# Schematic.net
KiCad netlist of a schematic drawn in EAGLE
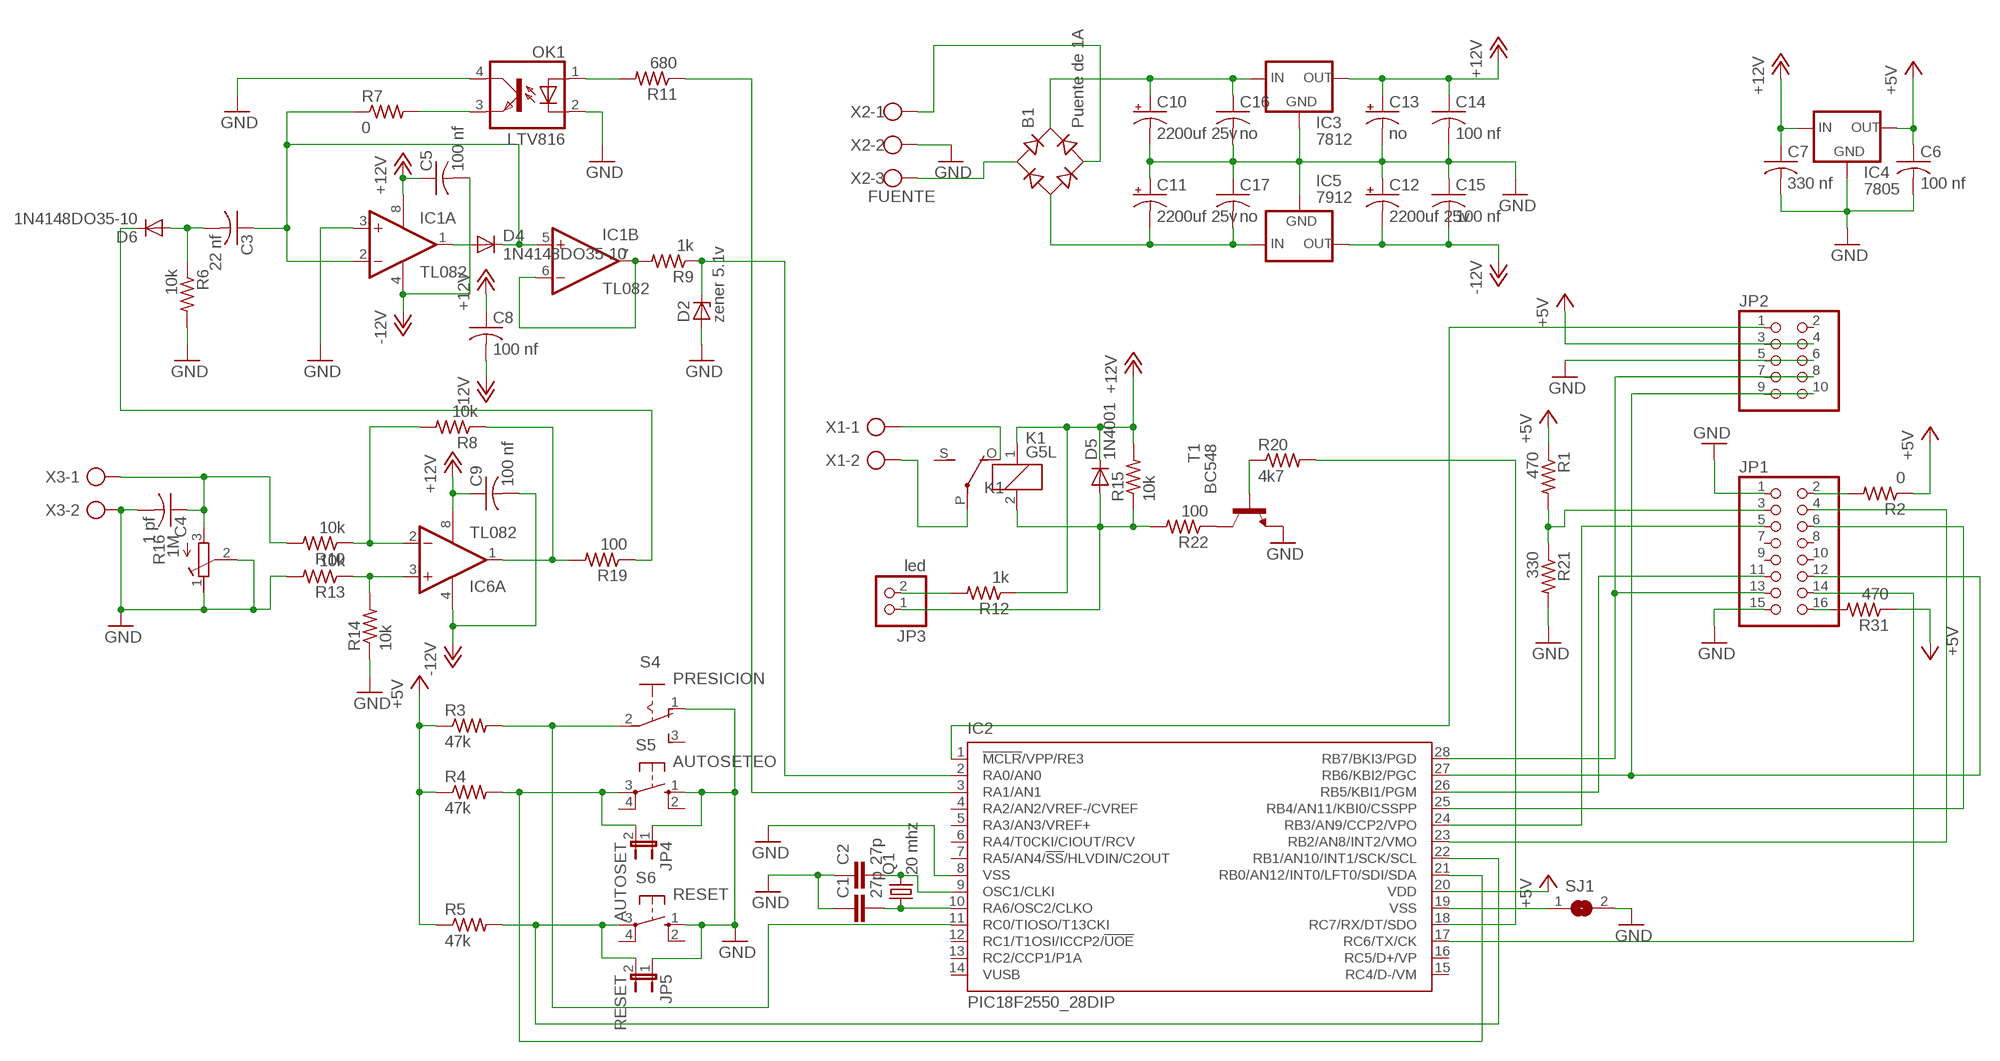
[diagram p0: schematic, sheet 1]

(export (version "E")
  (design (tool "Eeschema 10.0.6"))
  (components
    (comp (ref "B1")
      (value "Puente de 1A")
      (footprint "eagle-import:RB1A")
      (libsource (lib "eagle-import") (part "RB1A"))
    )
    (comp (ref "C1")
      (value "27p")
      (footprint "eagle-import:C050-024X044")
      (libsource (lib "eagle-import") (part "C-EU050-024X044"))
    )
    (comp (ref "C2")
      (value "27p")
      (footprint "eagle-import:C050-024X044")
      (libsource (lib "eagle-import") (part "C-EU050-024X044"))
    )
    (comp (ref "C3")
      (value "22 nf")
      (footprint "eagle-import:C050-024X044")
      (libsource (lib "eagle-import") (part "C-US050-024X044"))
    )
    (comp (ref "C4")
      (value "1 pf")
      (footprint "eagle-import:C050-024X044")
      (libsource (lib "eagle-import") (part "C-US050-024X044"))
    )
    (comp (ref "C5")
      (value "100 nf")
      (footprint "eagle-import:C050-024X044")
      (libsource (lib "eagle-import") (part "C-US050-024X044"))
    )
    (comp (ref "C6")
      (value "100 nf")
      (footprint "eagle-import:C050-024X044")
      (libsource (lib "eagle-import") (part "C-US050-024X044"))
    )
    (comp (ref "C7")
      (value "330 nf")
      (footprint "eagle-import:C050-024X044")
      (libsource (lib "eagle-import") (part "C-US050-024X044"))
    )
    (comp (ref "C8")
      (value "100 nf")
      (footprint "eagle-import:C050-024X044")
      (libsource (lib "eagle-import") (part "C-US050-024X044"))
    )
    (comp (ref "C9")
      (value "100 nf")
      (footprint "eagle-import:C050-024X044")
      (libsource (lib "eagle-import") (part "C-US050-024X044"))
    )
    (comp (ref "C10")
      (value "2200uf 25v")
      (footprint "eagle-import:E7,5-16")
      (libsource (lib "eagle-import") (part "CPOL-USE7.5-16"))
    )
    (comp (ref "C11")
      (value "2200uf 25v")
      (footprint "eagle-import:E7,5-16")
      (libsource (lib "eagle-import") (part "CPOL-USE7.5-16"))
    )
    (comp (ref "C12")
      (value "2200uf 25v")
      (footprint "eagle-import:E7,5-16")
      (libsource (lib "eagle-import") (part "CPOL-USE7.5-16"))
    )
    (comp (ref "C13")
      (value "no")
      (footprint "eagle-import:E7,5-16")
      (libsource (lib "eagle-import") (part "CPOL-USE7.5-16"))
    )
    (comp (ref "C14")
      (value "100 nf")
      (footprint "eagle-import:C050-024X044")
      (libsource (lib "eagle-import") (part "C-US050-024X044"))
    )
    (comp (ref "C15")
      (value "100 nf")
      (footprint "eagle-import:C050-024X044")
      (libsource (lib "eagle-import") (part "C-US050-024X044"))
    )
    (comp (ref "C16")
      (value "no")
      (footprint "eagle-import:C050-024X044")
      (libsource (lib "eagle-import") (part "C-US050-024X044"))
    )
    (comp (ref "C17")
      (value "no")
      (footprint "eagle-import:C050-024X044")
      (libsource (lib "eagle-import") (part "C-US050-024X044"))
    )
    (comp (ref "D2")
      (value "zener 5.1v")
      (footprint "eagle-import:P1Z12")
      (libsource (lib "eagle-import") (part "ZENER-DIODEP1-Z12"))
    )
    (comp (ref "D4")
      (value "1N4148DO35-10")
      (footprint "eagle-import:DO35-10")
      (libsource (lib "eagle-import") (part "1N4148DO35-10"))
    )
    (comp (ref "D5")
      (value "1N4001")
      (footprint "eagle-import:DO41-10")
      (libsource (lib "eagle-import") (part "1N4004"))
    )
    (comp (ref "D6")
      (value "1N4148DO35-10")
      (footprint "eagle-import:DO35-10")
      (libsource (lib "eagle-import") (part "1N4148DO35-10"))
    )
    (comp (ref "IC1")
      (value "TL082")
      (footprint "eagle-import:DIL08")
      (libsource (lib "eagle-import") (part "4558NLM"))
    )
    (comp (ref "IC2")
      (value "PIC18F2550_28DIP")
      (footprint "eagle-import:DIL28-3")
      (libsource (lib "eagle-import") (part "PIC18F2_28DIP550"))
    )
    (comp (ref "IC3")
      (value "7812")
      (footprint "eagle-import:78XXS")
      (libsource (lib "eagle-import") (part "78XXS"))
    )
    (comp (ref "IC4")
      (value "7805")
      (footprint "eagle-import:78XXS")
      (libsource (lib "eagle-import") (part "78XXS"))
    )
    (comp (ref "IC5")
      (value "7912")
      (footprint "eagle-import:79XXS")
      (libsource (lib "eagle-import") (part "79XXS"))
    )
    (comp (ref "IC6")
      (value "TL082")
      (footprint "eagle-import:DIL08")
      (libsource (lib "eagle-import") (part "4558NLM"))
    )
    (comp (ref "JP1")
      (value "PINHD-2X8")
      (footprint "eagle-import:2X08")
      (libsource (lib "eagle-import") (part "PINHD-2X8"))
    )
    (comp (ref "JP2")
      (value "PINHD-2X5")
      (footprint "eagle-import:2X05")
      (libsource (lib "eagle-import") (part "PINHD-2X5"))
    )
    (comp (ref "JP3")
      (value "led")
      (footprint "eagle-import:1X02")
      (libsource (lib "eagle-import") (part "PINHD-1X2"))
    )
    (comp (ref "JP4")
      (value "AUTOSET")
      (footprint "eagle-import:JP1")
      (libsource (lib "eagle-import") (part "JP1E"))
    )
    (comp (ref "JP5")
      (value "RESET")
      (footprint "eagle-import:JP1")
      (libsource (lib "eagle-import") (part "JP1E"))
    )
    (comp (ref "K1")
      (value "G5L")
      (footprint "eagle-import:G5LE")
      (libsource (lib "eagle-import") (part "G5L"))
    )
    (comp (ref "OK1")
      (value "LTV816")
      (footprint "eagle-import:DIL04")
      (libsource (lib "eagle-import") (part "LTV816"))
    )
    (comp (ref "Q1")
      (value "20 mhz")
      (footprint "eagle-import:HC49_S")
      (libsource (lib "eagle-import") (part "CRYSTALHC49S"))
    )
    (comp (ref "R1")
      (value "470")
      (footprint "eagle-import:0207_10")
      (libsource (lib "eagle-import") (part "R-US_0207/10"))
    )
    (comp (ref "R2")
      (value "0")
      (footprint "eagle-import:0207_10")
      (libsource (lib "eagle-import") (part "R-US_0207/10"))
    )
    (comp (ref "R3")
      (value "47k")
      (footprint "eagle-import:0207_10")
      (libsource (lib "eagle-import") (part "R-US_0207/10"))
    )
    (comp (ref "R4")
      (value "47k")
      (footprint "eagle-import:0207_10")
      (libsource (lib "eagle-import") (part "R-US_0207/10"))
    )
    (comp (ref "R5")
      (value "47k")
      (footprint "eagle-import:0207_10")
      (libsource (lib "eagle-import") (part "R-US_0207/10"))
    )
    (comp (ref "R6")
      (value "10k")
      (footprint "eagle-import:0207_10")
      (libsource (lib "eagle-import") (part "R-US_0207/10"))
    )
    (comp (ref "R7")
      (value "0")
      (footprint "eagle-import:0207_10")
      (libsource (lib "eagle-import") (part "R-US_0207/10"))
    )
    (comp (ref "R8")
      (value "10k")
      (footprint "eagle-import:0207_10")
      (libsource (lib "eagle-import") (part "R-US_0207/10"))
    )
    (comp (ref "R9")
      (value "1k")
      (footprint "eagle-import:0207_10")
      (libsource (lib "eagle-import") (part "R-US_0207/10"))
    )
    (comp (ref "R10")
      (value "10k")
      (footprint "eagle-import:0207_10")
      (libsource (lib "eagle-import") (part "R-US_0207/10"))
    )
    (comp (ref "R11")
      (value "680")
      (footprint "eagle-import:0207_10")
      (libsource (lib "eagle-import") (part "R-US_0207/10"))
    )
    (comp (ref "R12")
      (value "1k")
      (footprint "eagle-import:0207_10")
      (libsource (lib "eagle-import") (part "R-US_0207/10"))
    )
    (comp (ref "R13")
      (value "10k")
      (footprint "eagle-import:0207_10")
      (libsource (lib "eagle-import") (part "R-US_0207/10"))
    )
    (comp (ref "R14")
      (value "10k")
      (footprint "eagle-import:0207_10")
      (libsource (lib "eagle-import") (part "R-US_0207/10"))
    )
    (comp (ref "R15")
      (value "10k")
      (footprint "eagle-import:0207_10")
      (libsource (lib "eagle-import") (part "R-US_0207/10"))
    )
    (comp (ref "R16")
      (value "1M")
      (footprint "eagle-import:RTRIMT93YA")
      (libsource (lib "eagle-import") (part "R-TRIMMT93YA"))
    )
    (comp (ref "R19")
      (value "100")
      (footprint "eagle-import:0207_10")
      (libsource (lib "eagle-import") (part "R-US_0207/10"))
    )
    (comp (ref "R20")
      (value "4k7")
      (footprint "eagle-import:0207_10")
      (libsource (lib "eagle-import") (part "R-US_0207/10"))
    )
    (comp (ref "R21")
      (value "330")
      (footprint "eagle-import:0207_10")
      (libsource (lib "eagle-import") (part "R-US_0207/10"))
    )
    (comp (ref "R22")
      (value "100")
      (footprint "eagle-import:0207_10")
      (libsource (lib "eagle-import") (part "R-US_0207/10"))
    )
    (comp (ref "R31")
      (value "470")
      (footprint "eagle-import:0207_10")
      (libsource (lib "eagle-import") (part "R-US_0207/10"))
    )
    (comp (ref "S4")
      (value "PRESICION")
      (footprint "eagle-import:M251")
      (libsource (lib "eagle-import") (part "M251"))
    )
    (comp (ref "S5")
      (value "AUTOSETEO")
      (footprint "eagle-import:B3F-10XX")
      (libsource (lib "eagle-import") (part "10-XX"))
    )
    (comp (ref "S6")
      (value "RESET")
      (footprint "eagle-import:B3F-10XX")
      (libsource (lib "eagle-import") (part "10-XX"))
    )
    (comp (ref "SJ1") (value "SJ") (footprint "eagle-import:SJ") (libsource (lib "eagle-import") (part "SJ")))
    (comp (ref "T1")
      (value "BC548")
      (footprint "eagle-import:TO92")
      (libsource (lib "eagle-import") (part "BC547"))
    )
    (comp (ref "X1")
      (value "AK300/2")
      (footprint "eagle-import:AK300_2")
      (libsource (lib "eagle-import") (part "AK300/2"))
    )
    (comp (ref "X2")
      (value "FUENTE")
      (footprint "eagle-import:W237-103")
      (libsource (lib "eagle-import") (part "W237-103"))
    )
    (comp (ref "X3")
      (value "AK300/2")
      (footprint "eagle-import:AK300_2")
      (libsource (lib "eagle-import") (part "AK300/2"))
    )
  )
  (nets
    (net (code "1") (name "+5V") (class "Default")
      (node (ref "C6") (pin "1") (pinfunction "1_1") (pintype "passive"))
      (node (ref "IC2") (pin "20") (pinfunction "VDD_20") (pintype "power_in"))
      (node (ref "IC4") (pin "OUT") (pinfunction "OUT_OUT") (pintype "passive"))
      (node (ref "JP2") (pin "3") (pinfunction "3_3") (pintype "passive"))
      (node (ref "JP2") (pin "4") (pinfunction "4_4") (pintype "passive"))
      (node (ref "R1") (pin "1") (pinfunction "1_1") (pintype "passive"))
      (node (ref "R2") (pin "1") (pinfunction "1_1") (pintype "passive"))
      (node (ref "R3") (pin "1") (pinfunction "1_1") (pintype "passive"))
      (node (ref "R31") (pin "1") (pinfunction "1_1") (pintype "passive"))
      (node (ref "R4") (pin "1") (pinfunction "1_1") (pintype "passive"))
      (node (ref "R5") (pin "1") (pinfunction "1_1") (pintype "passive"))
    )
    (net (code "2") (name "+12V") (class "Default")
      (node (ref "C13") (pin "+") (pinfunction "+_+") (pintype "passive"))
      (node (ref "C14") (pin "1") (pinfunction "1_1") (pintype "passive"))
      (node (ref "C5") (pin "1") (pinfunction "1_1") (pintype "passive"))
      (node (ref "C7") (pin "1") (pinfunction "1_1") (pintype "passive"))
      (node (ref "C8") (pin "1") (pinfunction "1_1") (pintype "passive"))
      (node (ref "C9") (pin "1") (pinfunction "1_1") (pintype "passive"))
      (node (ref "D5") (pin "C") (pinfunction "C_C") (pintype "passive"))
      (node (ref "IC1") (pin "8") (pinfunction "V+_8") (pintype "power_in"))
      (node (ref "IC3") (pin "OUT") (pinfunction "OUT_OUT") (pintype "passive"))
      (node (ref "IC4") (pin "IN") (pinfunction "IN_IN") (pintype "input"))
      (node (ref "IC6") (pin "8") (pinfunction "V+_8") (pintype "power_in"))
      (node (ref "K1") (pin "1") (pinfunction "1_1") (pintype "passive"))
      (node (ref "R12") (pin "1") (pinfunction "1_1") (pintype "passive"))
      (node (ref "R15") (pin "2") (pinfunction "2_2") (pintype "passive"))
    )
    (net (code "3") (name "-12V") (class "Default")
      (node (ref "C12") (pin "-") (pinfunction "-_-") (pintype "passive"))
      (node (ref "C15") (pin "2") (pinfunction "2_2") (pintype "passive"))
      (node (ref "C5") (pin "2") (pinfunction "2_2") (pintype "passive"))
      (node (ref "C8") (pin "2") (pinfunction "2_2") (pintype "passive"))
      (node (ref "C9") (pin "2") (pinfunction "2_2") (pintype "passive"))
      (node (ref "IC1") (pin "4") (pinfunction "V-_4") (pintype "power_in"))
      (node (ref "IC5") (pin "OUT") (pinfunction "OUT_OUT") (pintype "passive"))
      (node (ref "IC6") (pin "4") (pinfunction "V-_4") (pintype "power_in"))
    )
    (net (code "4") (name "GND") (class "Default")
      (node (ref "C1") (pin "1") (pinfunction "1_1") (pintype "passive"))
      (node (ref "C10") (pin "-") (pinfunction "-_-") (pintype "passive"))
      (node (ref "C11") (pin "+") (pinfunction "+_+") (pintype "passive"))
      (node (ref "C12") (pin "+") (pinfunction "+_+") (pintype "passive"))
      (node (ref "C13") (pin "-") (pinfunction "-_-") (pintype "passive"))
      (node (ref "C14") (pin "2") (pinfunction "2_2") (pintype "passive"))
      (node (ref "C15") (pin "1") (pinfunction "1_1") (pintype "passive"))
      (node (ref "C16") (pin "2") (pinfunction "2_2") (pintype "passive"))
      (node (ref "C17") (pin "1") (pinfunction "1_1") (pintype "passive"))
      (node (ref "C2") (pin "1") (pinfunction "1_1") (pintype "passive"))
      (node (ref "C4") (pin "2") (pinfunction "2_2") (pintype "passive"))
      (node (ref "C6") (pin "2") (pinfunction "2_2") (pintype "passive"))
      (node (ref "C7") (pin "2") (pinfunction "2_2") (pintype "passive"))
      (node (ref "D2") (pin "A") (pinfunction "A_A") (pintype "passive"))
      (node (ref "IC1") (pin "3") (pinfunction "+IN_3") (pintype "input"))
      (node (ref "IC2") (pin "8") (pinfunction "VSS_8") (pintype "power_in"))
      (node (ref "IC3") (pin "GND") (pinfunction "GND_GND") (pintype "input"))
      (node (ref "IC4") (pin "GND") (pinfunction "GND_GND") (pintype "input"))
      (node (ref "IC5") (pin "GND") (pinfunction "GND_GND") (pintype "input"))
      (node (ref "JP1") (pin "1") (pinfunction "1_1") (pintype "passive"))
      (node (ref "JP1") (pin "15") (pinfunction "15_15") (pintype "passive"))
      (node (ref "JP2") (pin "5") (pinfunction "5_5") (pintype "passive"))
      (node (ref "JP2") (pin "6") (pinfunction "6_6") (pintype "passive"))
      (node (ref "JP4") (pin "1") (pinfunction "1_1") (pintype "passive"))
      (node (ref "JP5") (pin "1") (pinfunction "1_1") (pintype "passive"))
      (node (ref "OK1") (pin "2") (pinfunction "C_2") (pintype "passive"))
      (node (ref "OK1") (pin "4") (pinfunction "COL_4") (pintype "passive"))
      (node (ref "R13") (pin "2") (pinfunction "2_2") (pintype "passive"))
      (node (ref "R14") (pin "1") (pinfunction "1_1") (pintype "passive"))
      (node (ref "R16") (pin "1") (pinfunction "A_1") (pintype "passive"))
      (node (ref "R16") (pin "2") (pinfunction "S_2") (pintype "passive"))
      (node (ref "R21") (pin "2") (pinfunction "2_2") (pintype "passive"))
      (node (ref "R6") (pin "2") (pinfunction "2_2") (pintype "passive"))
      (node (ref "S4") (pin "1") (pinfunction "O_1") (pintype "passive"))
      (node (ref "S5") (pin "1") (pinfunction "S_1") (pintype "passive"))
      (node (ref "S6") (pin "1") (pinfunction "S_1") (pintype "passive"))
      (node (ref "SJ1") (pin "2") (pinfunction "2_2") (pintype "passive"))
      (node (ref "T1") (pin "1") (pinfunction "E_1") (pintype "passive"))
      (node (ref "X2") (pin "2") (pinfunction "KL_2") (pintype "passive"))
      (node (ref "X3") (pin "2") (pinfunction "KL_2") (pintype "passive"))
    )
    (net (code "5") (name "Net-(B1-Pad+)") (class "Default")
      (node (ref "B1") (pin "+") (pinfunction "+_+") (pintype "passive"))
      (node (ref "C10") (pin "+") (pinfunction "+_+") (pintype "passive"))
      (node (ref "C16") (pin "1") (pinfunction "1_1") (pintype "passive"))
      (node (ref "IC3") (pin "IN") (pinfunction "IN_IN") (pintype "input"))
    )
    (net (code "6") (name "Net-(B1-Pad-)") (class "Default")
      (node (ref "B1") (pin "-") (pinfunction "-_-") (pintype "passive"))
      (node (ref "C11") (pin "-") (pinfunction "-_-") (pintype "passive"))
      (node (ref "C17") (pin "2") (pinfunction "2_2") (pintype "passive"))
      (node (ref "IC5") (pin "IN") (pinfunction "IN_IN") (pintype "input"))
    )
    (net (code "7") (name "Net-(C3-Pad2)") (class "Default")
      (node (ref "C3") (pin "2") (pinfunction "2_2") (pintype "passive"))
      (node (ref "D6") (pin "A") (pinfunction "A_A") (pintype "passive"))
      (node (ref "R6") (pin "1") (pinfunction "1_1") (pintype "passive"))
    )
    (net (code "8") (name "Net-(D5-PadA)") (class "Default")
      (node (ref "D5") (pin "A") (pinfunction "A_A") (pintype "passive"))
      (node (ref "JP3") (pin "1") (pinfunction "1_1") (pintype "passive"))
      (node (ref "K1") (pin "2") (pinfunction "2_2") (pintype "passive"))
      (node (ref "R15") (pin "1") (pinfunction "1_1") (pintype "passive"))
      (node (ref "R22") (pin "2") (pinfunction "2_2") (pintype "passive"))
    )
    (net (code "9") (name "Net-(D6-PadC)") (class "Default")
      (node (ref "D6") (pin "C") (pinfunction "C_C") (pintype "passive"))
      (node (ref "R19") (pin "1") (pinfunction "1_1") (pintype "passive"))
    )
    (net (code "10") (name "Net-(IC1A--IN)") (class "Default")
      (node (ref "C3") (pin "1") (pinfunction "1_1") (pintype "passive"))
      (node (ref "D4") (pin "C") (pinfunction "C_C") (pintype "passive"))
      (node (ref "IC1") (pin "2") (pinfunction "-IN_2") (pintype "input"))
      (node (ref "IC1") (pin "5") (pinfunction "+IN_5") (pintype "input"))
      (node (ref "R7") (pin "1") (pinfunction "1_1") (pintype "passive"))
    )
    (net (code "11") (name "Net-(IC1A-OUT)") (class "Default")
      (node (ref "D4") (pin "A") (pinfunction "A_A") (pintype "passive"))
      (node (ref "IC1") (pin "1") (pinfunction "OUT_1") (pintype "output"))
    )
    (net (code "12") (name "Net-(IC1B--IN)") (class "Default")
      (node (ref "IC1") (pin "6") (pinfunction "-IN_6") (pintype "input"))
      (node (ref "IC1") (pin "7") (pinfunction "OUT_7") (pintype "output"))
      (node (ref "R9") (pin "2") (pinfunction "2_2") (pintype "passive"))
    )
    (net (code "13") (name "Net-(IC2-OSC1{slash}CLKI)") (class "Default")
      (node (ref "C2") (pin "2") (pinfunction "2_2") (pintype "passive"))
      (node (ref "IC2") (pin "9") (pinfunction "OSC1/CLKI_9") (pintype "input"))
      (node (ref "Q1") (pin "2") (pinfunction "2_2") (pintype "passive"))
    )
    (net (code "14") (name "Net-(IC2-RA0{slash}AN0)") (class "Default")
      (node (ref "D2") (pin "C") (pinfunction "C_C") (pintype "passive"))
      (node (ref "IC2") (pin "2") (pinfunction "RA0/AN0_2") (pintype "bidirectional"))
      (node (ref "R9") (pin "1") (pinfunction "1_1") (pintype "passive"))
    )
    (net (code "15") (name "Net-(IC2-RA1{slash}AN1)") (class "Default")
      (node (ref "IC2") (pin "3") (pinfunction "RA1/AN1_3") (pintype "bidirectional"))
      (node (ref "R11") (pin "1") (pinfunction "1_1") (pintype "passive"))
    )
    (net (code "16") (name "Net-(IC2-RA6{slash}OSC2{slash}CLKO)") (class "Default")
      (node (ref "C1") (pin "2") (pinfunction "2_2") (pintype "passive"))
      (node (ref "IC2") (pin "10") (pinfunction "RA6/OSC2/CLKO_10") (pintype "output"))
      (node (ref "Q1") (pin "1") (pinfunction "1_1") (pintype "passive"))
    )
    (net (code "17") (name "Net-(IC2-RB0{slash}AN12{slash}INT0{slash}LFT0{slash}SDI{slash}SDA)") (class "Default")
      (node (ref "IC2") (pin "21") (pinfunction "RB0/AN12/INT0/LFT0/SDI/SDA_21") (pintype "bidirectional"))
      (node (ref "JP4") (pin "2") (pinfunction "2_2") (pintype "passive"))
      (node (ref "R4") (pin "2") (pinfunction "2_2") (pintype "passive"))
      (node (ref "S5") (pin "3") (pinfunction "P_3") (pintype "passive"))
    )
    (net (code "18") (name "Net-(IC2-RB1{slash}AN10{slash}INT1{slash}SCK{slash}SCL)") (class "Default")
      (node (ref "IC2") (pin "22") (pinfunction "RB1/AN10/INT1/SCK/SCL_22") (pintype "bidirectional"))
      (node (ref "JP5") (pin "2") (pinfunction "2_2") (pintype "passive"))
      (node (ref "R5") (pin "2") (pinfunction "2_2") (pintype "passive"))
      (node (ref "S6") (pin "3") (pinfunction "P_3") (pintype "passive"))
    )
    (net (code "19") (name "Net-(IC2-RB2{slash}AN8{slash}INT2{slash}VMO)") (class "Default")
      (node (ref "IC2") (pin "23") (pinfunction "RB2/AN8/INT2/VMO_23") (pintype "bidirectional"))
      (node (ref "JP1") (pin "4") (pinfunction "4_4") (pintype "passive"))
    )
    (net (code "20") (name "Net-(IC2-RB3{slash}AN9{slash}CCP2{slash}VPO)") (class "Default")
      (node (ref "IC2") (pin "24") (pinfunction "RB3/AN9/CCP2/VPO_24") (pintype "bidirectional"))
      (node (ref "JP1") (pin "5") (pinfunction "5_5") (pintype "passive"))
    )
    (net (code "21") (name "Net-(IC2-RB4{slash}AN11{slash}KBI0{slash}CSSPP)") (class "Default")
      (node (ref "IC2") (pin "25") (pinfunction "RB4/AN11/KBI0/CSSPP_25") (pintype "bidirectional"))
      (node (ref "JP1") (pin "6") (pinfunction "6_6") (pintype "passive"))
    )
    (net (code "22") (name "Net-(IC2-RB5{slash}KBI1{slash}PGM)") (class "Default")
      (node (ref "IC2") (pin "26") (pinfunction "RB5/KBI1/PGM_26") (pintype "bidirectional"))
      (node (ref "JP1") (pin "11") (pinfunction "11_11") (pintype "passive"))
    )
    (net (code "23") (name "Net-(IC2-RB6{slash}KBI2{slash}PGC)") (class "Default")
      (node (ref "IC2") (pin "27") (pinfunction "RB6/KBI2/PGC_27") (pintype "bidirectional"))
      (node (ref "JP1") (pin "12") (pinfunction "12_12") (pintype "passive"))
      (node (ref "JP2") (pin "10") (pinfunction "10_10") (pintype "passive"))
      (node (ref "JP2") (pin "9") (pinfunction "9_9") (pintype "passive"))
    )
    (net (code "24") (name "Net-(IC2-RB7{slash}BKI3{slash}PGD)") (class "Default")
      (node (ref "IC2") (pin "28") (pinfunction "RB7/BKI3/PGD_28") (pintype "bidirectional"))
      (node (ref "JP1") (pin "13") (pinfunction "13_13") (pintype "passive"))
      (node (ref "JP2") (pin "7") (pinfunction "7_7") (pintype "passive"))
      (node (ref "JP2") (pin "8") (pinfunction "8_8") (pintype "passive"))
    )
    (net (code "25") (name "Net-(IC2-RC0{slash}TIOSO{slash}T13CKI)") (class "Default")
      (node (ref "IC2") (pin "11") (pinfunction "RC0/TIOSO/T13CKI_11") (pintype "bidirectional"))
      (node (ref "R3") (pin "2") (pinfunction "2_2") (pintype "passive"))
      (node (ref "S4") (pin "2") (pinfunction "P_2") (pintype "passive"))
    )
    (net (code "26") (name "Net-(IC2-RC6{slash}TX{slash}CK)") (class "Default")
      (node (ref "IC2") (pin "17") (pinfunction "RC6/TX/CK_17") (pintype "bidirectional"))
      (node (ref "JP1") (pin "14") (pinfunction "14_14") (pintype "passive"))
    )
    (net (code "27") (name "Net-(IC2-RC7{slash}RX{slash}DT{slash}SDO)") (class "Default")
      (node (ref "IC2") (pin "18") (pinfunction "RC7/RX/DT/SDO_18") (pintype "bidirectional"))
      (node (ref "R20") (pin "2") (pinfunction "2_2") (pintype "passive"))
    )
    (net (code "28") (name "Net-(IC2-VSS-Pad19)") (class "Default")
      (node (ref "IC2") (pin "19") (pinfunction "VSS_19") (pintype "power_in"))
      (node (ref "SJ1") (pin "1") (pinfunction "1_1") (pintype "passive"))
    )
    (net (code "29") (name "Net-(IC2-~{MCLR}{slash}VPP{slash}RE3)") (class "Default")
      (node (ref "IC2") (pin "1") (pinfunction "~{MCLR}/VPP/RE3_1") (pintype "input"))
      (node (ref "JP2") (pin "1") (pinfunction "1_1") (pintype "passive"))
    )
    (net (code "30") (name "Net-(IC6A-+IN)") (class "Default")
      (node (ref "IC6") (pin "3") (pinfunction "+IN_3") (pintype "input"))
      (node (ref "R13") (pin "1") (pinfunction "1_1") (pintype "passive"))
      (node (ref "R14") (pin "2") (pinfunction "2_2") (pintype "passive"))
    )
    (net (code "31") (name "Net-(IC6A--IN)") (class "Default")
      (node (ref "IC6") (pin "2") (pinfunction "-IN_2") (pintype "input"))
      (node (ref "R10") (pin "1") (pinfunction "1_1") (pintype "passive"))
      (node (ref "R8") (pin "2") (pinfunction "2_2") (pintype "passive"))
    )
    (net (code "32") (name "Net-(IC6A-OUT)") (class "Default")
      (node (ref "IC6") (pin "1") (pinfunction "OUT_1") (pintype "output"))
      (node (ref "R19") (pin "2") (pinfunction "2_2") (pintype "passive"))
      (node (ref "R8") (pin "1") (pinfunction "1_1") (pintype "passive"))
    )
    (net (code "33") (name "Net-(JP1-Pad2)") (class "Default")
      (node (ref "JP1") (pin "2") (pinfunction "2_2") (pintype "passive"))
      (node (ref "R2") (pin "2") (pinfunction "2_2") (pintype "passive"))
    )
    (net (code "34") (name "Net-(JP1-Pad3)") (class "Default")
      (node (ref "JP1") (pin "3") (pinfunction "3_3") (pintype "passive"))
      (node (ref "R1") (pin "2") (pinfunction "2_2") (pintype "passive"))
      (node (ref "R21") (pin "1") (pinfunction "1_1") (pintype "passive"))
    )
    (net (code "35") (name "Net-(JP1-Pad16)") (class "Default")
      (node (ref "JP1") (pin "16") (pinfunction "16_16") (pintype "passive"))
      (node (ref "R31") (pin "2") (pinfunction "2_2") (pintype "passive"))
    )
    (net (code "36") (name "Net-(JP3-Pad2)") (class "Default")
      (node (ref "JP3") (pin "2") (pinfunction "2_2") (pintype "passive"))
      (node (ref "R12") (pin "2") (pinfunction "2_2") (pintype "passive"))
    )
    (net (code "37") (name "Net-(OK1-A)") (class "Default")
      (node (ref "OK1") (pin "1") (pinfunction "A_1") (pintype "passive"))
      (node (ref "R11") (pin "2") (pinfunction "2_2") (pintype "passive"))
    )
    (net (code "38") (name "Net-(OK1-EMIT)") (class "Default")
      (node (ref "OK1") (pin "3") (pinfunction "EMIT_3") (pintype "passive"))
      (node (ref "R7") (pin "2") (pinfunction "2_2") (pintype "passive"))
    )
    (net (code "39") (name "Net-(R16-E)") (class "Default")
      (node (ref "C4") (pin "1") (pinfunction "1_1") (pintype "passive"))
      (node (ref "R10") (pin "2") (pinfunction "2_2") (pintype "passive"))
      (node (ref "R16") (pin "3") (pinfunction "E_3") (pintype "passive"))
      (node (ref "X3") (pin "1") (pinfunction "KL_1") (pintype "passive"))
    )
    (net (code "40") (name "Net-(T1-B)") (class "Default")
      (node (ref "R20") (pin "1") (pinfunction "1_1") (pintype "passive"))
      (node (ref "T1") (pin "2") (pinfunction "B_2") (pintype "passive"))
    )
    (net (code "41") (name "Net-(T1-C)") (class "Default")
      (node (ref "R22") (pin "1") (pinfunction "1_1") (pintype "passive"))
      (node (ref "T1") (pin "3") (pinfunction "C_3") (pintype "passive"))
    )
    (net (code "42") (name "Net-(X1A-KL)") (class "Default")
      (node (ref "K1") (pin "O") (pinfunction "O_O") (pintype "passive"))
      (node (ref "X1") (pin "1") (pinfunction "KL_1") (pintype "passive"))
    )
    (net (code "43") (name "Net-(X1B-KL)") (class "Default")
      (node (ref "K1") (pin "P") (pinfunction "P_P") (pintype "passive"))
      (node (ref "X1") (pin "2") (pinfunction "KL_2") (pintype "passive"))
    )
    (net (code "44") (name "Net-(X2A-KL)") (class "Default")
      (node (ref "B1") (pin "AC2") (pinfunction "AC2_AC2") (pintype "passive"))
      (node (ref "X2") (pin "1") (pinfunction "KL_1") (pintype "passive"))
    )
    (net (code "45") (name "Net-(X2C-KL)") (class "Default")
      (node (ref "B1") (pin "AC1") (pinfunction "AC1_AC1") (pintype "passive"))
      (node (ref "X2") (pin "3") (pinfunction "KL_3") (pintype "passive"))
    )
    (net (code "46") (name "unconnected-(IC2-RA2{slash}AN2{slash}VREF-{slash}CVREF-Pad4)") (class "Default")
      (node (ref "IC2") (pin "4") (pinfunction "RA2/AN2/VREF-/CVREF_4") (pintype "bidirectional"))
    )
    (net (code "47") (name "unconnected-(IC2-RA3{slash}AN3{slash}VREF+-Pad5)") (class "Default")
      (node (ref "IC2") (pin "5") (pinfunction "RA3/AN3/VREF+_5") (pintype "bidirectional"))
    )
    (net (code "48") (name "unconnected-(IC2-RA4{slash}T0CKI{slash}CIOUT{slash}RCV-Pad6)") (class "Default")
      (node (ref "IC2") (pin "6") (pinfunction "RA4/T0CKI/CIOUT/RCV_6") (pintype "bidirectional"))
    )
    (net (code "49") (name "unconnected-(IC2-RA5{slash}AN4{slash}~{SS}{slash}HLVDIN{slash}C2OUT-Pad7)") (class "Default")
      (node (ref "IC2") (pin "7") (pinfunction "RA5/AN4/~{SS}/HLVDIN/C2OUT_7") (pintype "bidirectional"))
    )
    (net (code "50") (name "unconnected-(IC2-RC1{slash}T1OSI{slash}ICCP2{slash}~{UOE}-Pad12)") (class "Default")
      (node (ref "IC2") (pin "12") (pinfunction "RC1/T1OSI/ICCP2/~{UOE}_12") (pintype "bidirectional"))
    )
    (net (code "51") (name "unconnected-(IC2-RC2{slash}CCP1{slash}P1A-Pad13)") (class "Default")
      (node (ref "IC2") (pin "13") (pinfunction "RC2/CCP1/P1A_13") (pintype "bidirectional"))
    )
    (net (code "52") (name "unconnected-(IC2-RC4{slash}D-{slash}VM-Pad15)") (class "Default")
      (node (ref "IC2") (pin "15") (pinfunction "RC4/D-/VM_15") (pintype "bidirectional"))
    )
    (net (code "53") (name "unconnected-(IC2-RC5{slash}D+{slash}VP-Pad16)") (class "Default")
      (node (ref "IC2") (pin "16") (pinfunction "RC5/D+/VP_16") (pintype "bidirectional"))
    )
    (net (code "54") (name "unconnected-(IC2-VUSB-Pad14)") (class "Default")
      (node (ref "IC2") (pin "14") (pinfunction "VUSB_14") (pintype "bidirectional"))
    )
    (net (code "55") (name "unconnected-(JP1-Pad7)") (class "Default")
      (node (ref "JP1") (pin "7") (pinfunction "7_7") (pintype "passive"))
    )
    (net (code "56") (name "unconnected-(JP1-Pad8)") (class "Default")
      (node (ref "JP1") (pin "8") (pinfunction "8_8") (pintype "passive"))
    )
    (net (code "57") (name "unconnected-(JP1-Pad9)") (class "Default")
      (node (ref "JP1") (pin "9") (pinfunction "9_9") (pintype "passive"))
    )
    (net (code "58") (name "unconnected-(JP1-Pad10)") (class "Default")
      (node (ref "JP1") (pin "10") (pinfunction "10_10") (pintype "passive"))
    )
    (net (code "59") (name "unconnected-(JP2-Pad2)") (class "Default")
      (node (ref "JP2") (pin "2") (pinfunction "2_2") (pintype "passive"))
    )
    (net (code "60") (name "unconnected-(K1-PadS)") (class "Default")
      (node (ref "K1") (pin "S") (pinfunction "S_S") (pintype "passive"))
    )
    (net (code "61") (name "unconnected-(S4-S-Pad3)") (class "Default")
      (node (ref "S4") (pin "3") (pinfunction "S_3") (pintype "passive"))
    )
    (net (code "62") (name "unconnected-(S5-P1-Pad4)") (class "Default")
      (node (ref "S5") (pin "4") (pinfunction "P1_4") (pintype "passive"))
    )
    (net (code "63") (name "unconnected-(S5-S1-Pad2)") (class "Default")
      (node (ref "S5") (pin "2") (pinfunction "S1_2") (pintype "passive"))
    )
    (net (code "64") (name "unconnected-(S6-P1-Pad4)") (class "Default")
      (node (ref "S6") (pin "4") (pinfunction "P1_4") (pintype "passive"))
    )
    (net (code "65") (name "unconnected-(S6-S1-Pad2)") (class "Default")
      (node (ref "S6") (pin "2") (pinfunction "S1_2") (pintype "passive"))
    )
  )
)
